# Sheet1.net
KiCad netlist of a schematic drawn in Altium Designer
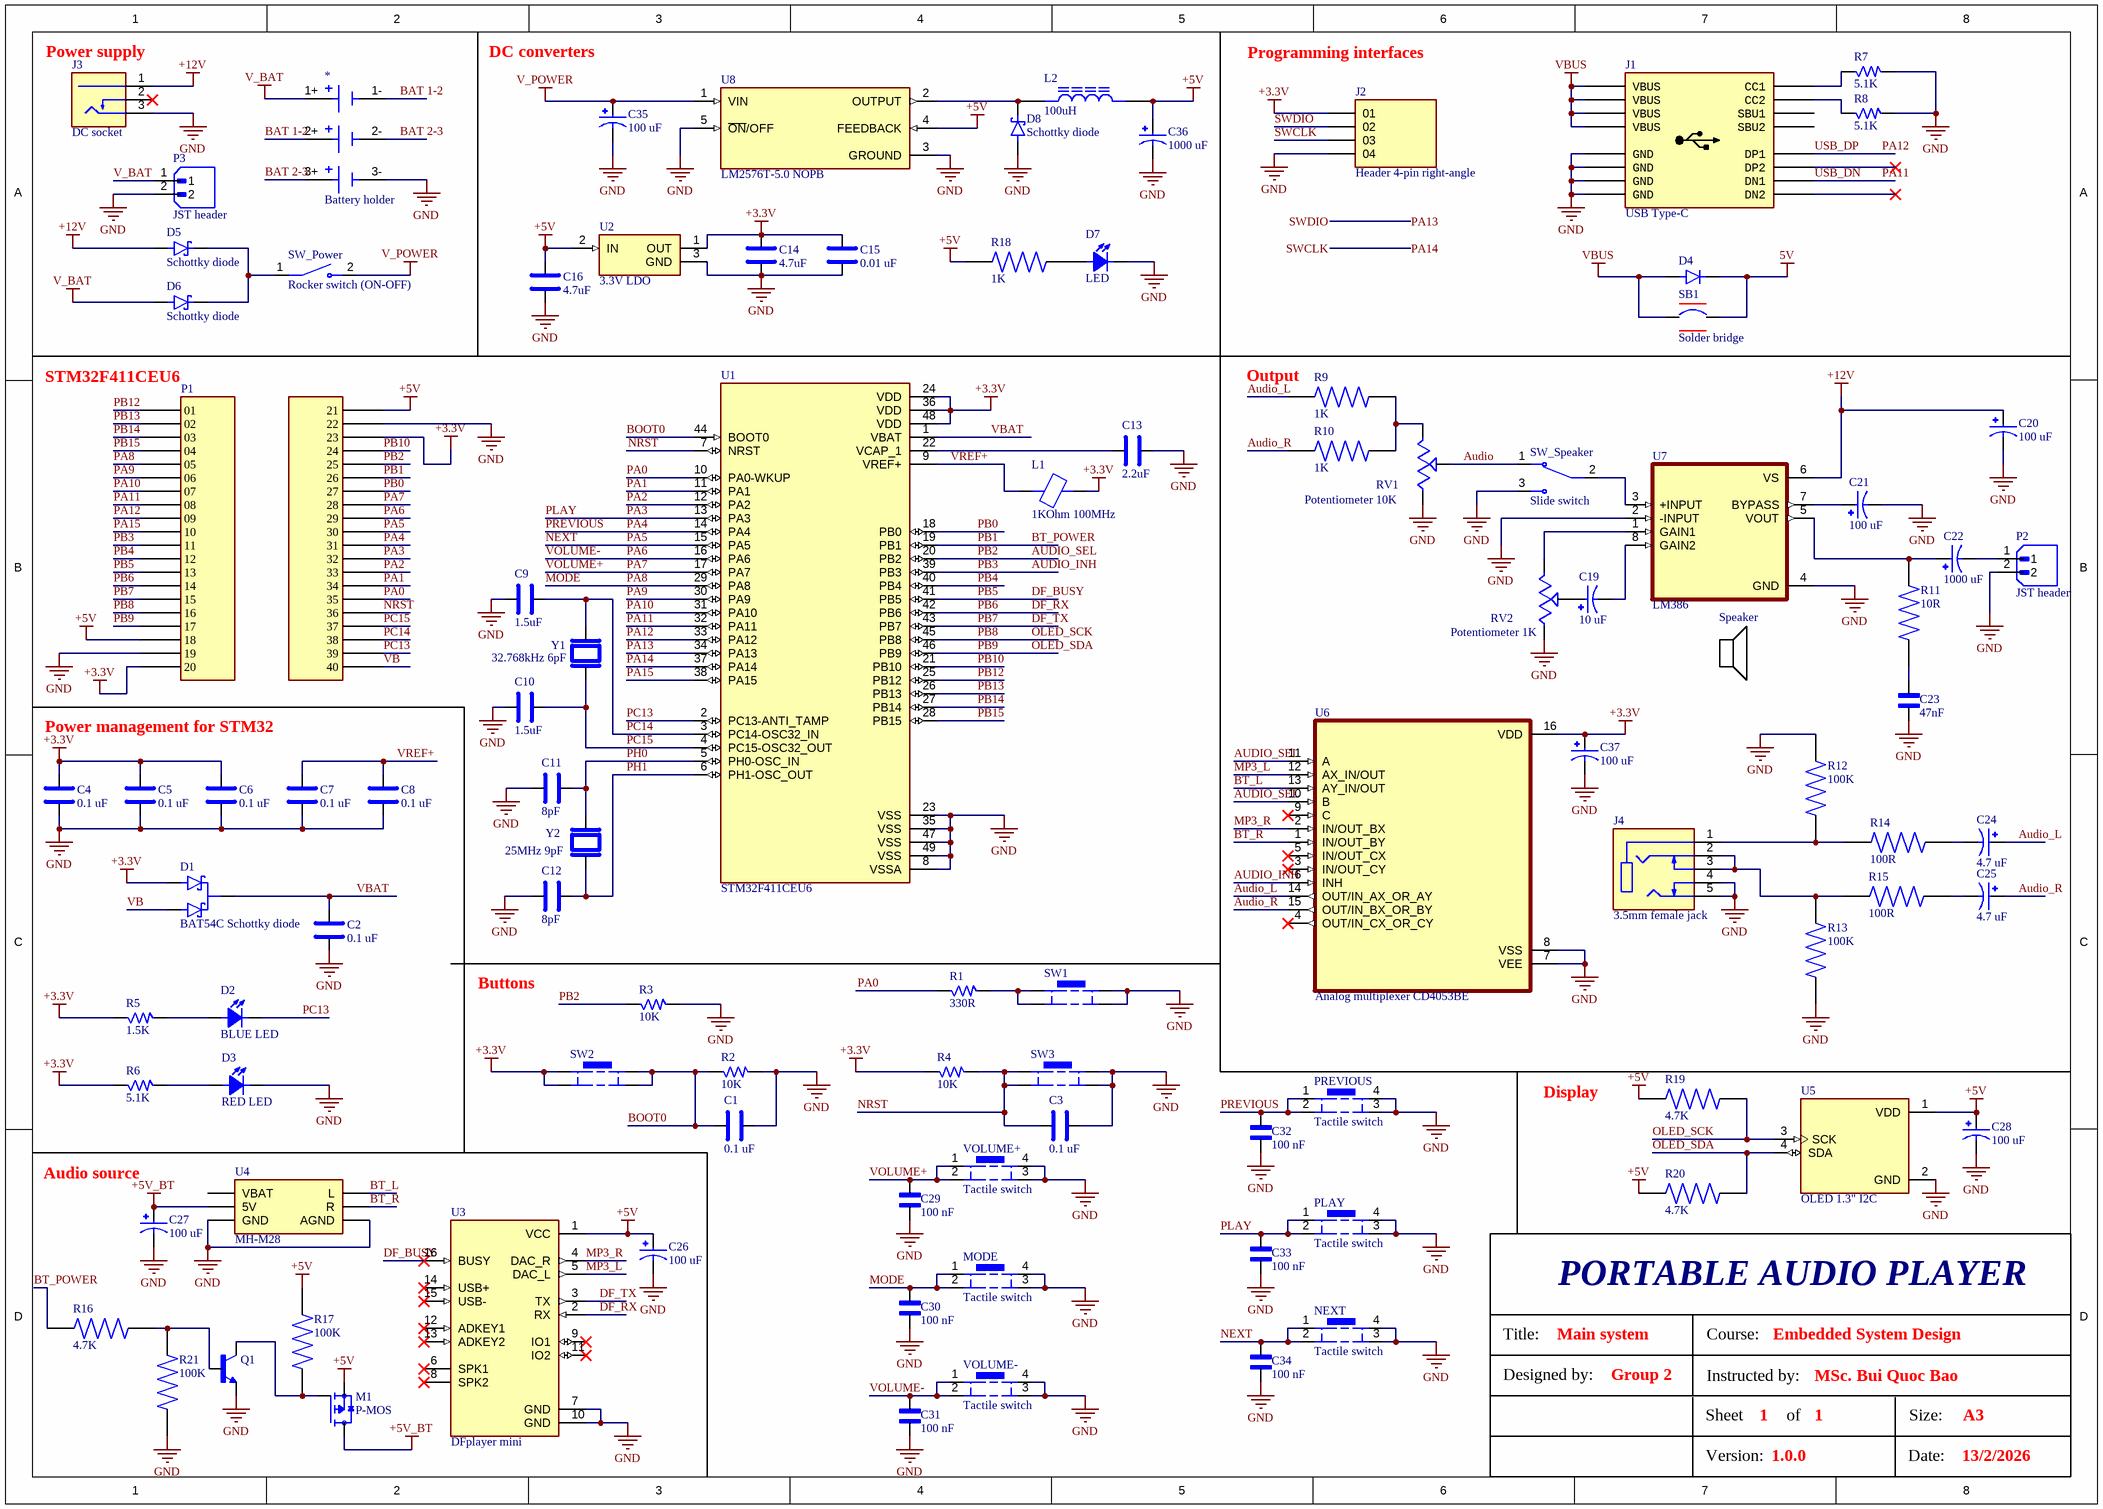
[diagram p0: Sheet1.SchDoc]

(export (version "E")
  (design (tool "Eeschema 10.0.6"))
  (components
    (comp (ref "*")
      (value "Battery holder")
      (footprint "BAT_BK-18650-PC6")
      (libsource (lib "Schlib1") (part "Battery holder"))
    )
    (comp (ref "C1") (value "0.1 uF") (footprint "CAP-CER-0603") (libsource (lib "Schlib1") (part "0.1 uF")))
    (comp (ref "C2") (value "0.1 uF") (footprint "CAP-CER-0603") (libsource (lib "Schlib1") (part "0.1 uF")))
    (comp (ref "C3") (value "0.1 uF") (footprint "CAP-CER-0603") (libsource (lib "Schlib1") (part "0.1 uF")))
    (comp (ref "C4") (value "0.1 uF") (footprint "CAP-CER-0603") (libsource (lib "Schlib1") (part "0.1 uF")))
    (comp (ref "C5") (value "0.1 uF") (footprint "CAP-CER-0603") (libsource (lib "Schlib1") (part "0.1 uF")))
    (comp (ref "C6") (value "0.1 uF") (footprint "CAP-CER-0603") (libsource (lib "Schlib1") (part "0.1 uF")))
    (comp (ref "C7") (value "0.1 uF") (footprint "CAP-CER-0603") (libsource (lib "Schlib1") (part "0.1 uF")))
    (comp (ref "C8") (value "0.1 uF") (footprint "CAP-CER-0603") (libsource (lib "Schlib1") (part "0.1 uF")))
    (comp (ref "C9") (value "1.5uF") (footprint "CAP-CER-0603") (libsource (lib "Schlib1") (part "1.5uF")))
    (comp (ref "C10") (value "1.5uF") (footprint "CAP-CER-0603") (libsource (lib "Schlib1") (part "1.5uF")))
    (comp (ref "C11") (value "8pF") (footprint "CAP-CER-0603") (libsource (lib "Schlib1") (part "8pF")))
    (comp (ref "C12") (value "8pF") (footprint "CAP-CER-0603") (libsource (lib "Schlib1") (part "8pF")))
    (comp (ref "C13") (value "2.2uF") (footprint "CAP-CER-0603") (libsource (lib "Schlib1") (part "2.2uF")))
    (comp (ref "C14") (value "4.7uF") (footprint "CAP-CER-0603") (libsource (lib "Schlib1") (part "4.7uF")))
    (comp (ref "C15")
      (value "0.01 uF")
      (footprint "CAP-CER-0603")
      (libsource (lib "Schlib1") (part "0.01 uF"))
    )
    (comp (ref "C16") (value "4.7uF") (footprint "CAP-CER-0603") (libsource (lib "Schlib1") (part "4.7uF")))
    (comp (ref "C19")
      (value "10 uF")
      (footprint "CAPPRD200W50D500H1100")
      (libsource (lib "Schlib1") (part "10 uF"))
    )
    (comp (ref "C20")
      (value "100 uF")
      (footprint "CAPPRD250W50D630H1120")
      (libsource (lib "") (part "100 uF_1"))
    )
    (comp (ref "C21")
      (value "100 uF")
      (footprint "CAPPRD250W50D630H1120")
      (libsource (lib "Schlib1") (part "100 uF"))
    )
    (comp (ref "C22")
      (value "1000 uF")
      (footprint "CAPPRD500W60D1000H2500")
      (libsource (lib "") (part "1000 uF_1"))
    )
    (comp (ref "C23")
      (value "47nF")
      (footprint "CAPRR254W50L508T317H508")
      (libsource (lib "Schlib1") (part "47nF"))
    )
    (comp (ref "C24")
      (value "4.7 uF")
      (footprint "CAPPRD200W50D500H1100")
      (libsource (lib "Schlib1") (part "4.7 uF"))
    )
    (comp (ref "C25")
      (value "4.7 uF")
      (footprint "CAPPRD200W50D500H1100")
      (libsource (lib "Schlib1") (part "4.7 uF"))
    )
    (comp (ref "C26")
      (value "100 uF")
      (footprint "CAPPRD250W50D630H1120")
      (libsource (lib "") (part "100 uF_1"))
    )
    (comp (ref "C27")
      (value "100 uF")
      (footprint "CAPPRD250W50D630H1120")
      (libsource (lib "") (part "100 uF_1"))
    )
    (comp (ref "C28")
      (value "100 uF")
      (footprint "CAPPRD250W50D630H1120")
      (libsource (lib "") (part "100 uF_1"))
    )
    (comp (ref "C29")
      (value "100 nF")
      (footprint "CAPRR254W54L381T254H466")
      (libsource (lib "Schlib1") (part "100 nF"))
    )
    (comp (ref "C30")
      (value "100 nF")
      (footprint "CAPRR254W54L381T254H466")
      (libsource (lib "Schlib1") (part "100 nF"))
    )
    (comp (ref "C31")
      (value "100 nF")
      (footprint "CAPRR254W54L381T254H466")
      (libsource (lib "Schlib1") (part "100 nF"))
    )
    (comp (ref "C32")
      (value "100 nF")
      (footprint "CAPRR254W54L381T254H466")
      (libsource (lib "Schlib1") (part "100 nF"))
    )
    (comp (ref "C33")
      (value "100 nF")
      (footprint "CAPRR254W54L381T254H466")
      (libsource (lib "Schlib1") (part "100 nF"))
    )
    (comp (ref "C34")
      (value "100 nF")
      (footprint "CAPRR254W54L381T254H466")
      (libsource (lib "Schlib1") (part "100 nF"))
    )
    (comp (ref "C35")
      (value "100 uF")
      (footprint "CAPPRD250W50D630H1120")
      (libsource (lib "") (part "100 uF_1"))
    )
    (comp (ref "C36")
      (value "1000 uF")
      (footprint "CAPPRD500W60D1000H2500")
      (libsource (lib "Schlib1") (part "1000 uF"))
    )
    (comp (ref "C37")
      (value "100 uF")
      (footprint "CAPPRD250W50D630H1120")
      (libsource (lib "") (part "100 uF_1"))
    )
    (comp (ref "D1")
      (value "BAT54C Schottky diode")
      (footprint "SOT95P237X112-3N")
      (libsource (lib "Schlib1") (part "BAT54C Schottky diode"))
    )
    (comp (ref "D2")
      (value "BLUE LED")
      (footprint "LED-SMD-0603")
      (libsource (lib "Schlib1") (part "BLUE LED"))
    )
    (comp (ref "D3")
      (value "RED LED")
      (footprint "LED-SMD-0603")
      (libsource (lib "Schlib1") (part "RED LED"))
    )
    (comp (ref "D4") (value "Diode") (footprint "DIOM5227X270N") (libsource (lib "Schlib1") (part "Diode")))
    (comp (ref "D5")
      (value "Schottky diode")
      (footprint "DIOAD1039W78L463D236")
      (libsource (lib "Schlib1") (part "Schottky diode"))
    )
    (comp (ref "D6")
      (value "Schottky diode")
      (footprint "DIOAD1039W78L463D236")
      (libsource (lib "Schlib1") (part "Schottky diode"))
    )
    (comp (ref "D7") (value "LED") (footprint "LED-TH-2.54mm") (libsource (lib "Schlib1") (part "LED")))
    (comp (ref "D8")
      (value "Schottky diode")
      (footprint "DIOAD1039W78L463D236")
      (libsource (lib "Schlib1") (part "Schottky diode"))
    )
    (comp (ref "J1")
      (value "USB Type-C")
      (footprint "TYPE-C-16POS")
      (libsource (lib "Schlib1") (part "USB Type-C"))
    )
    (comp (ref "J2")
      (value "Header 4-pin right-angle")
      (footprint "SAMTEC_HTSW-104-08-G-S-RA")
      (libsource (lib "Schlib1") (part "Header 4-pin right-angle"))
    )
    (comp (ref "J3")
      (value "DC socket")
      (footprint "GRAVITECH_CON-SOCJ-2155")
      (libsource (lib "Schlib1") (part "DC socket"))
    )
    (comp (ref "J4")
      (value "3.5mm female jack")
      (footprint "CLIFF_FC68133")
      (libsource (lib "Schlib1") (part "3.5mm female jack"))
    )
    (comp (ref "L1")
      (value "1KOhm 100MHz")
      (footprint "FERRITE-0603")
      (libsource (lib "Schlib1") (part "1KOhm 100MHz"))
    )
    (comp (ref "L2")
      (value "100uH")
      (footprint "IND_RLB9012-101KL")
      (libsource (lib "Schlib1") (part "100uH"))
    )
    (comp (ref "M1")
      (value "P-MOS")
      (footprint "TO254P1067X483X2286-3")
      (libsource (lib "Schlib1") (part "P-MOS"))
    )
    (comp (ref "MODE")
      (value "Tactile switch")
      (footprint "Tactice-Switch-TH-12x12")
      (libsource (lib "Schlib1") (part "Tactile switch"))
    )
    (comp (ref "NEXT")
      (value "Tactile switch")
      (footprint "Tactice-Switch-TH-12x12")
      (libsource (lib "Schlib1") (part "Tactile switch"))
    )
    (comp (ref "P1")
      (value "2x20 female header for mounting Blackpill board")
      (footprint "Blackpill board mounting headers")
      (libsource (lib "Schlib1") (part "2x20 female header for mounting Blackpill board"))
    )
    (comp (ref "P2")
      (value "JST header")
      (footprint "JST_B2B-XH-A")
      (libsource (lib "Schlib1") (part "JST header"))
    )
    (comp (ref "P3")
      (value "JST header")
      (footprint "JST_B2B-XH-A")
      (libsource (lib "Schlib1") (part "JST header"))
    )
    (comp (ref "PLAY")
      (value "Tactile switch")
      (footprint "Tactice-Switch-TH-12x12")
      (libsource (lib "Schlib1") (part "Tactile switch"))
    )
    (comp (ref "PREVIOUS")
      (value "Tactile switch")
      (footprint "Tactice-Switch-TH-12x12")
      (libsource (lib "Schlib1") (part "Tactile switch"))
    )
    (comp (ref "Q1")
      (value "NPN transistor")
      (footprint "TO92127P495H495-3")
      (libsource (lib "Schlib1") (part "NPN transistor"))
    )
    (comp (ref "R1") (value "330R") (footprint "RES-SMD-0603") (libsource (lib "Schlib1") (part "330R")))
    (comp (ref "R2") (value "10K") (footprint "RES-SMD-0603") (libsource (lib "Schlib1") (part "10K")))
    (comp (ref "R3") (value "10K") (footprint "RES-SMD-0603") (libsource (lib "Schlib1") (part "10K")))
    (comp (ref "R4") (value "10K") (footprint "RES-SMD-0603") (libsource (lib "Schlib1") (part "10K")))
    (comp (ref "R5") (value "1.5K") (footprint "RES-SMD-0603") (libsource (lib "Schlib1") (part "1.5K")))
    (comp (ref "R6") (value "5.1K") (footprint "RES-SMD-0603") (libsource (lib "Schlib1") (part "5.1K")))
    (comp (ref "R7") (value "5.1K") (footprint "RES-SMD-0603") (libsource (lib "Schlib1") (part "5.1K")))
    (comp (ref "R8") (value "5.1K") (footprint "RES-SMD-0603") (libsource (lib "Schlib1") (part "5.1K")))
    (comp (ref "R9") (value "1K") (footprint "RESAD1100W55L680D260") (libsource (lib "Schlib1") (part "1K")))
    (comp (ref "R10") (value "1K") (footprint "RESAD1100W55L680D260") (libsource (lib "Schlib1") (part "1K")))
    (comp (ref "R11")
      (value "10R")
      (footprint "RESAD1100W55L680D260")
      (libsource (lib "Schlib1") (part "10R"))
    )
    (comp (ref "R12")
      (value "100K")
      (footprint "RESAD1100W55L680D260")
      (libsource (lib "Schlib1") (part "100K"))
    )
    (comp (ref "R13")
      (value "100K")
      (footprint "RESAD1100W55L680D260")
      (libsource (lib "Schlib1") (part "100K"))
    )
    (comp (ref "R14")
      (value "100R")
      (footprint "RESAD1100W55L680D260")
      (libsource (lib "Schlib1") (part "100R"))
    )
    (comp (ref "R15")
      (value "100R")
      (footprint "RESAD1100W55L680D260")
      (libsource (lib "Schlib1") (part "100R"))
    )
    (comp (ref "R16")
      (value "4.7K")
      (footprint "RESAD1100W55L680D260")
      (libsource (lib "Schlib1") (part "4.7K"))
    )
    (comp (ref "R17")
      (value "100K")
      (footprint "RESAD1100W55L680D260")
      (libsource (lib "Schlib1") (part "100K"))
    )
    (comp (ref "R18") (value "1K") (footprint "RESAD1100W55L680D260") (libsource (lib "Schlib1") (part "1K")))
    (comp (ref "R19")
      (value "4.7K")
      (footprint "RESAD1100W55L680D260")
      (libsource (lib "Schlib1") (part "4.7K"))
    )
    (comp (ref "R20")
      (value "4.7K")
      (footprint "RESAD1100W55L680D260")
      (libsource (lib "Schlib1") (part "4.7K"))
    )
    (comp (ref "R21")
      (value "100K")
      (footprint "RESAD1100W55L680D260")
      (libsource (lib "Schlib1") (part "100K"))
    )
    (comp (ref "RV1")
      (value "Potentiometer 10K")
      (footprint "TRIM_WH148-1A-2-18T-L20")
      (libsource (lib "Schlib1") (part "Potentiometer 10K"))
    )
    (comp (ref "RV2")
      (value "Potentiometer 1K")
      (footprint "TRIM_WH148-1A-2-18T-L20")
      (libsource (lib "Schlib1") (part "Potentiometer 1K"))
    )
    (comp (ref "SB1")
      (value "Solder bridge")
      (footprint "SOLDER_BRIDGE")
      (libsource (lib "Schlib1") (part "Solder bridge"))
    )
    (comp (ref "Speaker")
      (value "Speaker")
      (footprint "50mm speaker")
      (libsource (lib "Schlib1") (part "Speaker"))
    )
    (comp (ref "SW1")
      (value "SW_small_rectangular")
      (footprint "SW_SKRPACE010")
      (libsource (lib "Schlib1") (part "SW_small_rectangular"))
    )
    (comp (ref "SW2")
      (value "SW_small_rectangular")
      (footprint "SW_SKRPACE010")
      (libsource (lib "Schlib1") (part "SW_small_rectangular"))
    )
    (comp (ref "SW3")
      (value "SW_small_rectangular")
      (footprint "SW_SKRPACE010")
      (libsource (lib "Schlib1") (part "SW_small_rectangular"))
    )
    (comp (ref "SW_Power")
      (value "Rocker switch (ON-OFF)")
      (footprint "Rocker switch (ON-OFF)")
      (libsource (lib "Schlib1") (part "Rocker switch (ON-OFF)"))
    )
    (comp (ref "SW_Speaker")
      (value "Slide switch")
      (footprint "SW_SLW-1276864-4A-D")
      (libsource (lib "Schlib1") (part "Slide switch"))
    )
    (comp (ref "U1")
      (value "STM32F411CEU6")
      (footprint "QFN50P700X700X60-49N")
      (libsource (lib "Schlib1") (part "STM32F411CEU6"))
    )
    (comp (ref "U2") (value "3.3V LDO") (footprint "SOT23-3") (libsource (lib "Schlib1") (part "3.3V LDO")))
    (comp (ref "U3")
      (value "DFplayer mini")
      (footprint "MODULE_DFR0299")
      (libsource (lib "Schlib1") (part "DFplayer mini"))
    )
    (comp (ref "U4") (value "MH-M28") (footprint "MH-M28") (libsource (lib "Schlib1") (part "MH-M28")))
    (comp (ref "U5")
      (value "OLED 1.3\" I2C")
      (footprint "LCD_OLED_128X64_1.3_I2C")
      (libsource (lib "Schlib1") (part "OLED 1.3{dblquote} I2C"))
    )
    (comp (ref "U6")
      (value "Analog multiplexer CD4053BE")
      (footprint "DIP_16")
      (libsource (lib "Schlib1") (part "Analog multiplexer CD4053BE"))
    )
    (comp (ref "U7") (value "LM386") (footprint "DIP_8") (libsource (lib "Schlib1") (part "LM386")))
    (comp (ref "U8")
      (value "LM2576T-5.0 NOPB")
      (footprint "TO170P1067X483X1651-5")
      (libsource (lib "Schlib1") (part "LM2576T-5.0 NOPB"))
    )
    (comp (ref "VOLUME+")
      (value "Tactile switch")
      (footprint "Tactice-Switch-TH-12x12")
      (libsource (lib "Schlib1") (part "Tactile switch"))
    )
    (comp (ref "VOLUME-")
      (value "Tactile switch")
      (footprint "Tactice-Switch-TH-12x12")
      (libsource (lib "Schlib1") (part "Tactile switch"))
    )
    (comp (ref "Y1")
      (value "32.768kHz 6pF")
      (footprint "XTAL_CM8V-T1A-32.768KHZ-6PF-20PPM-TA-QC")
      (libsource (lib "Schlib1") (part "32.768kHz 6pF"))
    )
    (comp (ref "Y2")
      (value "25MHz 9pF")
      (footprint "XTAL_SXT2249BB16-25.000MT")
      (libsource (lib "Schlib1") (part "25MHz 9pF"))
    )
  )
  (nets
    (net (code "1") (name "+3.3V") (class "Default")
      (node (ref "C14") (pin "2") (pintype "passive"))
      (node (ref "C15") (pin "2") (pintype "passive"))
      (node (ref "C37") (pin "P") (pinfunction "P_P") (pintype "passive"))
      (node (ref "C4") (pin "2") (pintype "passive"))
      (node (ref "C5") (pin "2") (pintype "passive"))
      (node (ref "C6") (pin "2") (pintype "passive"))
      (node (ref "D1") (pin "1") (pinfunction "1_1") (pintype "passive"))
      (node (ref "J2") (pin "01") (pinfunction "01_01") (pintype "passive"))
      (node (ref "L1") (pin "2") (pinfunction "2_2") (pintype "passive"))
      (node (ref "P1") (pin "20") (pinfunction "20_20") (pintype "passive"))
      (node (ref "P1") (pin "23") (pinfunction "23_23") (pintype "passive"))
      (node (ref "R4") (pin "1") (pinfunction "1_1") (pintype "passive"))
      (node (ref "R5") (pin "1") (pinfunction "1_1") (pintype "passive"))
      (node (ref "R6") (pin "1") (pinfunction "1_1") (pintype "passive"))
      (node (ref "SW2") (pin "1") (pintype "passive"))
      (node (ref "SW2") (pin "2") (pintype "passive"))
      (node (ref "U1") (pin "24") (pinfunction "VDD_24") (pintype "power_in"))
      (node (ref "U1") (pin "36") (pinfunction "VDD_36") (pintype "power_in"))
      (node (ref "U1") (pin "48") (pinfunction "VDD_48") (pintype "power_in"))
      (node (ref "U2") (pin "1") (pinfunction "OUT_1") (pintype "power_in"))
      (node (ref "U6") (pin "16") (pinfunction "VDD_16") (pintype "power_in"))
    )
    (net (code "2") (name "+5V") (class "Default")
      (node (ref "C16") (pin "2") (pintype "passive"))
      (node (ref "C26") (pin "P") (pinfunction "P_P") (pintype "passive"))
      (node (ref "C28") (pin "P") (pinfunction "P_P") (pintype "passive"))
      (node (ref "C36") (pin "P") (pinfunction "P_P") (pintype "passive"))
      (node (ref "L2") (pin "2") (pinfunction "2_2") (pintype "passive"))
      (node (ref "M1") (pin "3") (pinfunction "S_3") (pintype "passive"))
      (node (ref "P1") (pin "18") (pinfunction "18_18") (pintype "passive"))
      (node (ref "P1") (pin "21") (pinfunction "21_21") (pintype "passive"))
      (node (ref "R17") (pin "2") (pinfunction "2_2") (pintype "passive"))
      (node (ref "R18") (pin "1") (pinfunction "1_1") (pintype "passive"))
      (node (ref "R19") (pin "2") (pinfunction "2_2") (pintype "passive"))
      (node (ref "R20") (pin "1") (pinfunction "1_1") (pintype "passive"))
      (node (ref "U2") (pin "2") (pinfunction "IN_2") (pintype "input"))
      (node (ref "U3") (pin "1") (pinfunction "VCC_1") (pintype "power_in"))
      (node (ref "U5") (pin "1") (pinfunction "VDD_1") (pintype "power_in"))
      (node (ref "U8") (pin "4") (pinfunction "FEEDBACK_4") (pintype "input"))
    )
    (net (code "3") (name "+5V_BT") (class "Default")
      (node (ref "C27") (pin "P") (pinfunction "P_P") (pintype "passive"))
      (node (ref "M1") (pin "2") (pinfunction "D_2") (pintype "passive"))
      (node (ref "U4") (pin "5V") (pinfunction "5V_5V") (pintype "passive"))
    )
    (net (code "4") (name "+12V") (class "Default")
      (node (ref "C20") (pin "P") (pinfunction "P_P") (pintype "passive"))
      (node (ref "D5") (pin "2") (pinfunction "A_2") (pintype "passive"))
      (node (ref "J3") (pin "1") (pinfunction "1_1") (pintype "passive"))
      (node (ref "U7") (pin "6") (pinfunction "VS_6") (pintype "power_in"))
    )
    (net (code "5") (name "/AUDIO_INH") (class "Default")
      (node (ref "P1") (pin "11") (pinfunction "11_11") (pintype "passive"))
      (node (ref "U1") (pin "39") (pinfunction "PB3_39") (pintype "bidirectional"))
      (node (ref "U6") (pin "6") (pinfunction "INH_6") (pintype "input"))
    )
    (net (code "6") (name "/AUDIO_SEL") (class "Default")
      (node (ref "P1") (pin "25") (pinfunction "25_25") (pintype "passive"))
      (node (ref "R3") (pin "1") (pinfunction "1_1") (pintype "passive"))
      (node (ref "U1") (pin "20") (pinfunction "PB2_20") (pintype "bidirectional"))
      (node (ref "U6") (pin "10") (pinfunction "B_10") (pintype "input"))
      (node (ref "U6") (pin "11") (pinfunction "A_11") (pintype "input"))
    )
    (net (code "7") (name "/Audio") (class "Default")
      (node (ref "RV1") (pin "2") (pinfunction "2_2") (pintype "passive"))
      (node (ref "SW_Speaker") (pin "1") (pinfunction "1_1") (pintype "passive"))
    )
    (net (code "8") (name "/Audio_L") (class "Default")
      (node (ref "C24") (pin "P") (pinfunction "P_P") (pintype "passive"))
      (node (ref "R9") (pin "1") (pinfunction "1_1") (pintype "passive"))
      (node (ref "U6") (pin "14") (pinfunction "OUT/IN_AX_OR_AY_14") (pintype "output"))
    )
    (net (code "9") (name "/Audio_R") (class "Default")
      (node (ref "C25") (pin "P") (pinfunction "P_P") (pintype "passive"))
      (node (ref "R10") (pin "1") (pinfunction "1_1") (pintype "passive"))
      (node (ref "U6") (pin "15") (pinfunction "OUT/IN_BX_OR_BY_15") (pintype "output"))
    )
    (net (code "10") (name "/BAT 1-2") (class "Default")
      (node (ref "*") (pin "1-") (pinfunction "1-_1-") (pintype "passive"))
      (node (ref "*") (pin "2+") (pinfunction "2+_2+") (pintype "passive"))
    )
    (net (code "11") (name "/BAT 2-3") (class "Default")
      (node (ref "*") (pin "2-") (pinfunction "2-_2-") (pintype "passive"))
      (node (ref "*") (pin "3+") (pinfunction "3+_3+") (pintype "passive"))
    )
    (net (code "12") (name "/BOOT0") (class "Default")
      (node (ref "C1") (pin "1") (pintype "passive"))
      (node (ref "R2") (pin "1") (pinfunction "1_1") (pintype "passive"))
      (node (ref "SW2") (pin "3") (pintype "passive"))
      (node (ref "SW2") (pin "4") (pintype "passive"))
      (node (ref "U1") (pin "44") (pinfunction "BOOT0_44") (pintype "input"))
    )
    (net (code "13") (name "/BT_L") (class "Default")
      (node (ref "U4") (pin "L") (pinfunction "L_L") (pintype "passive"))
      (node (ref "U6") (pin "13") (pinfunction "AY_IN/OUT_13") (pintype "input"))
    )
    (net (code "14") (name "/BT_POWER") (class "Default")
      (node (ref "P1") (pin "26") (pinfunction "26_26") (pintype "passive"))
      (node (ref "R16") (pin "1") (pinfunction "1_1") (pintype "passive"))
      (node (ref "U1") (pin "19") (pinfunction "PB1_19") (pintype "bidirectional"))
    )
    (net (code "15") (name "/BT_R") (class "Default")
      (node (ref "U4") (pin "R") (pinfunction "R_R") (pintype "passive"))
      (node (ref "U6") (pin "1") (pinfunction "IN/OUT_BY_1") (pintype "input"))
    )
    (net (code "16") (name "/DF_BUSY") (class "Default")
      (node (ref "P1") (pin "13") (pinfunction "13_13") (pintype "passive"))
      (node (ref "U1") (pin "41") (pinfunction "PB5_41") (pintype "bidirectional"))
      (node (ref "U3") (pin "16") (pinfunction "BUSY_16") (pintype "input"))
    )
    (net (code "17") (name "/DF_RX") (class "Default")
      (node (ref "P1") (pin "14") (pinfunction "14_14") (pintype "passive"))
      (node (ref "U1") (pin "42") (pinfunction "PB6_42") (pintype "bidirectional"))
      (node (ref "U3") (pin "2") (pinfunction "RX_2") (pintype "input"))
    )
    (net (code "18") (name "/DF_TX") (class "Default")
      (node (ref "P1") (pin "15") (pinfunction "15_15") (pintype "passive"))
      (node (ref "U1") (pin "43") (pinfunction "PB7_43") (pintype "bidirectional"))
      (node (ref "U3") (pin "3") (pinfunction "TX_3") (pintype "output"))
    )
    (net (code "19") (name "/MODE") (class "Default")
      (node (ref "C30") (pin "2") (pinfunction "2_2") (pintype "passive"))
      (node (ref "MODE") (pin "1") (pinfunction "1_1") (pintype "passive"))
      (node (ref "MODE") (pin "2") (pinfunction "2_2") (pintype "passive"))
      (node (ref "P1") (pin "5") (pinfunction "05_5") (pintype "passive"))
      (node (ref "U1") (pin "29") (pinfunction "PA8_29") (pintype "bidirectional"))
    )
    (net (code "20") (name "/MP3_L") (class "Default")
      (node (ref "U3") (pin "5") (pinfunction "DAC_L_5") (pintype "output"))
      (node (ref "U6") (pin "12") (pinfunction "AX_IN/OUT_12") (pintype "input"))
    )
    (net (code "21") (name "/MP3_R") (class "Default")
      (node (ref "U3") (pin "4") (pinfunction "DAC_R_4") (pintype "output"))
      (node (ref "U6") (pin "2") (pinfunction "IN/OUT_BX_2") (pintype "input"))
    )
    (net (code "22") (name "/NEXT") (class "Default")
      (node (ref "C34") (pin "2") (pinfunction "2_2") (pintype "passive"))
      (node (ref "NEXT") (pin "1") (pinfunction "1_1") (pintype "passive"))
      (node (ref "NEXT") (pin "2") (pinfunction "2_2") (pintype "passive"))
      (node (ref "P1") (pin "30") (pinfunction "30_30") (pintype "passive"))
      (node (ref "U1") (pin "15") (pinfunction "PA5_15") (pintype "bidirectional"))
    )
    (net (code "23") (name "/NRST") (class "Default")
      (node (ref "C3") (pin "1") (pintype "passive"))
      (node (ref "P1") (pin "36") (pinfunction "36_36") (pintype "passive"))
      (node (ref "R4") (pin "2") (pinfunction "2_2") (pintype "passive"))
      (node (ref "SW3") (pin "1") (pintype "passive"))
      (node (ref "SW3") (pin "2") (pintype "passive"))
      (node (ref "U1") (pin "7") (pinfunction "NRST_7") (pintype "bidirectional"))
    )
    (net (code "24") (name "/OLED_SCK") (class "Default")
      (node (ref "P1") (pin "16") (pinfunction "16_16") (pintype "passive"))
      (node (ref "R19") (pin "1") (pinfunction "1_1") (pintype "passive"))
      (node (ref "U1") (pin "45") (pinfunction "PB8_45") (pintype "bidirectional"))
      (node (ref "U5") (pin "3") (pinfunction "SCK_3") (pintype "input"))
    )
    (net (code "25") (name "/OLED_SDA") (class "Default")
      (node (ref "P1") (pin "17") (pinfunction "17_17") (pintype "passive"))
      (node (ref "R20") (pin "2") (pinfunction "2_2") (pintype "passive"))
      (node (ref "U1") (pin "46") (pinfunction "PB9_46") (pintype "bidirectional"))
      (node (ref "U5") (pin "4") (pinfunction "SDA_4") (pintype "bidirectional"))
    )
    (net (code "26") (name "/PA0") (class "Default")
      (node (ref "P1") (pin "35") (pinfunction "35_35") (pintype "passive"))
      (node (ref "R1") (pin "1") (pinfunction "1_1") (pintype "passive"))
      (node (ref "U1") (pin "10") (pinfunction "PA0-WKUP_10") (pintype "bidirectional"))
    )
    (net (code "27") (name "/PA1") (class "Default")
      (node (ref "P1") (pin "34") (pinfunction "34_34") (pintype "passive"))
      (node (ref "U1") (pin "11") (pinfunction "PA1_11") (pintype "bidirectional"))
    )
    (net (code "28") (name "/PA2") (class "Default")
      (node (ref "P1") (pin "33") (pinfunction "33_33") (pintype "passive"))
      (node (ref "U1") (pin "12") (pinfunction "PA2_12") (pintype "bidirectional"))
    )
    (net (code "29") (name "/PA3") (class "Default")
      (node (ref "C33") (pin "2") (pinfunction "2_2") (pintype "passive"))
      (node (ref "P1") (pin "32") (pinfunction "32_32") (pintype "passive"))
      (node (ref "PLAY") (pin "1") (pinfunction "1_1") (pintype "passive"))
      (node (ref "PLAY") (pin "2") (pinfunction "2_2") (pintype "passive"))
      (node (ref "U1") (pin "13") (pinfunction "PA3_13") (pintype "bidirectional"))
    )
    (net (code "30") (name "/PA4") (class "Default")
      (node (ref "C32") (pin "2") (pinfunction "2_2") (pintype "passive"))
      (node (ref "P1") (pin "31") (pinfunction "31_31") (pintype "passive"))
      (node (ref "PREVIOUS") (pin "1") (pinfunction "1_1") (pintype "passive"))
      (node (ref "PREVIOUS") (pin "2") (pinfunction "2_2") (pintype "passive"))
      (node (ref "U1") (pin "14") (pinfunction "PA4_14") (pintype "bidirectional"))
    )
    (net (code "31") (name "/PA6") (class "Default")
      (node (ref "C31") (pin "2") (pinfunction "2_2") (pintype "passive"))
      (node (ref "P1") (pin "29") (pinfunction "29_29") (pintype "passive"))
      (node (ref "U1") (pin "16") (pinfunction "PA6_16") (pintype "bidirectional"))
      (node (ref "VOLUME-") (pin "1") (pinfunction "1_1") (pintype "passive"))
      (node (ref "VOLUME-") (pin "2") (pinfunction "2_2") (pintype "passive"))
    )
    (net (code "32") (name "/PA7") (class "Default")
      (node (ref "C29") (pin "2") (pinfunction "2_2") (pintype "passive"))
      (node (ref "P1") (pin "28") (pinfunction "28_28") (pintype "passive"))
      (node (ref "U1") (pin "17") (pinfunction "PA7_17") (pintype "bidirectional"))
      (node (ref "VOLUME+") (pin "1") (pinfunction "1_1") (pintype "passive"))
      (node (ref "VOLUME+") (pin "2") (pinfunction "2_2") (pintype "passive"))
    )
    (net (code "33") (name "/PA9") (class "Default")
      (node (ref "P1") (pin "6") (pinfunction "06_6") (pintype "passive"))
      (node (ref "U1") (pin "30") (pinfunction "PA9_30") (pintype "bidirectional"))
    )
    (net (code "34") (name "/PA10") (class "Default")
      (node (ref "P1") (pin "7") (pinfunction "07_7") (pintype "passive"))
      (node (ref "U1") (pin "31") (pinfunction "PA10_31") (pintype "bidirectional"))
    )
    (net (code "35") (name "/PA11") (class "Default")
      (node (ref "J1") (pin "A7") (pinfunction "DN1_A7") (pintype "passive"))
      (node (ref "P1") (pin "8") (pinfunction "08_8") (pintype "passive"))
      (node (ref "U1") (pin "32") (pinfunction "PA11_32") (pintype "bidirectional"))
    )
    (net (code "36") (name "/PA12") (class "Default")
      (node (ref "J1") (pin "A6") (pinfunction "DP1_A6") (pintype "passive"))
      (node (ref "P1") (pin "9") (pinfunction "09_9") (pintype "passive"))
      (node (ref "U1") (pin "33") (pinfunction "PA12_33") (pintype "bidirectional"))
    )
    (net (code "37") (name "/PA13") (class "Default")
      (node (ref "J2") (pin "02") (pinfunction "02_02") (pintype "passive"))
      (node (ref "U1") (pin "34") (pinfunction "PA13_34") (pintype "bidirectional"))
    )
    (net (code "38") (name "/PA14") (class "Default")
      (node (ref "J2") (pin "03") (pinfunction "03_03") (pintype "passive"))
      (node (ref "U1") (pin "37") (pinfunction "PA14_37") (pintype "bidirectional"))
    )
    (net (code "39") (name "/PA15") (class "Default")
      (node (ref "P1") (pin "10") (pinfunction "10_10") (pintype "passive"))
      (node (ref "U1") (pin "38") (pinfunction "PA15_38") (pintype "bidirectional"))
    )
    (net (code "40") (name "/PB0") (class "Default")
      (node (ref "P1") (pin "27") (pinfunction "27_27") (pintype "passive"))
      (node (ref "U1") (pin "18") (pinfunction "PB0_18") (pintype "bidirectional"))
    )
    (net (code "41") (name "/PB4") (class "Default")
      (node (ref "P1") (pin "12") (pinfunction "12_12") (pintype "passive"))
      (node (ref "U1") (pin "40") (pinfunction "PB4_40") (pintype "bidirectional"))
    )
    (net (code "42") (name "/PB10") (class "Default")
      (node (ref "P1") (pin "24") (pinfunction "24_24") (pintype "passive"))
      (node (ref "U1") (pin "21") (pinfunction "PB10_21") (pintype "bidirectional"))
    )
    (net (code "43") (name "/PB12") (class "Default")
      (node (ref "P1") (pin "1") (pinfunction "01_1") (pintype "passive"))
      (node (ref "U1") (pin "25") (pinfunction "PB12_25") (pintype "bidirectional"))
    )
    (net (code "44") (name "/PB13") (class "Default")
      (node (ref "P1") (pin "2") (pinfunction "02_2") (pintype "passive"))
      (node (ref "U1") (pin "26") (pinfunction "PB13_26") (pintype "bidirectional"))
    )
    (net (code "45") (name "/PB14") (class "Default")
      (node (ref "P1") (pin "3") (pinfunction "03_3") (pintype "passive"))
      (node (ref "U1") (pin "27") (pinfunction "PB14_27") (pintype "bidirectional"))
    )
    (net (code "46") (name "/PB15") (class "Default")
      (node (ref "P1") (pin "4") (pinfunction "04_4") (pintype "passive"))
      (node (ref "U1") (pin "28") (pinfunction "PB15_28") (pintype "bidirectional"))
    )
    (net (code "47") (name "/PC13") (class "Default")
      (node (ref "D2") (pin "2") (pinfunction "K_2") (pintype "passive"))
      (node (ref "P1") (pin "39") (pinfunction "39_39") (pintype "passive"))
      (node (ref "U1") (pin "2") (pinfunction "PC13-ANTI_TAMP_2") (pintype "bidirectional"))
    )
    (net (code "48") (name "/PC14") (class "Default")
      (node (ref "C9") (pin "2") (pintype "passive"))
      (node (ref "P1") (pin "38") (pinfunction "38_38") (pintype "passive"))
      (node (ref "U1") (pin "3") (pinfunction "PC14-OSC32_IN_3") (pintype "bidirectional"))
      (node (ref "Y1") (pin "2") (pinfunction "2_2") (pintype "passive"))
    )
    (net (code "49") (name "/PC15") (class "Default")
      (node (ref "C10") (pin "2") (pintype "passive"))
      (node (ref "P1") (pin "37") (pinfunction "37_37") (pintype "passive"))
      (node (ref "U1") (pin "4") (pinfunction "PC15-OSC32_OUT_4") (pintype "bidirectional"))
      (node (ref "Y1") (pin "1") (pinfunction "1_1") (pintype "passive"))
    )
    (net (code "50") (name "/PH0") (class "Default")
      (node (ref "C11") (pin "2") (pintype "passive"))
      (node (ref "U1") (pin "5") (pinfunction "PH0-OSC_IN_5") (pintype "bidirectional"))
      (node (ref "Y2") (pin "3") (pinfunction "3_3") (pintype "passive"))
    )
    (net (code "51") (name "/PH1") (class "Default")
      (node (ref "C12") (pin "2") (pintype "passive"))
      (node (ref "U1") (pin "6") (pinfunction "PH1-OSC_OUT_6") (pintype "bidirectional"))
      (node (ref "Y2") (pin "1") (pinfunction "1_1") (pintype "passive"))
    )
    (net (code "52") (name "/VB") (class "Default")
      (node (ref "D1") (pin "2") (pinfunction "2_2") (pintype "passive"))
      (node (ref "P1") (pin "40") (pinfunction "40_40") (pintype "passive"))
    )
    (net (code "53") (name "/VBAT") (class "Default")
      (node (ref "C2") (pin "2") (pintype "passive"))
      (node (ref "D1") (pin "3") (pinfunction "3_3") (pintype "passive"))
      (node (ref "U1") (pin "1") (pinfunction "VBAT_1") (pintype "power_in"))
    )
    (net (code "54") (name "/VREF+") (class "Default")
      (node (ref "C7") (pin "2") (pintype "passive"))
      (node (ref "C8") (pin "2") (pintype "passive"))
      (node (ref "L1") (pin "1") (pinfunction "1_1") (pintype "passive"))
      (node (ref "U1") (pin "9") (pinfunction "VREF+_9") (pintype "power_in"))
    )
    (net (code "55") (name "5V") (class "Default")
      (node (ref "D4") (pin "C") (pinfunction "K_C") (pintype "passive"))
      (node (ref "SB1") (pin "2") (pinfunction "2_2") (pintype "passive"))
    )
    (net (code "56") (name "GND") (class "Default")
      (node (ref "*") (pin "3-") (pinfunction "3-_3-") (pintype "passive"))
      (node (ref "C1") (pin "2") (pintype "passive"))
      (node (ref "C10") (pin "1") (pintype "passive"))
      (node (ref "C11") (pin "1") (pintype "passive"))
      (node (ref "C12") (pin "1") (pintype "passive"))
      (node (ref "C13") (pin "2") (pintype "passive"))
      (node (ref "C14") (pin "1") (pintype "passive"))
      (node (ref "C15") (pin "1") (pintype "passive"))
      (node (ref "C16") (pin "1") (pintype "passive"))
      (node (ref "C2") (pin "1") (pintype "passive"))
      (node (ref "C20") (pin "N") (pinfunction "N_N") (pintype "passive"))
      (node (ref "C21") (pin "N") (pinfunction "N_N") (pintype "passive"))
      (node (ref "C23") (pin "1") (pinfunction "1_1") (pintype "passive"))
      (node (ref "C26") (pin "N") (pinfunction "N_N") (pintype "passive"))
      (node (ref "C27") (pin "N") (pinfunction "N_N") (pintype "passive"))
      (node (ref "C28") (pin "N") (pinfunction "N_N") (pintype "passive"))
      (node (ref "C29") (pin "1") (pinfunction "1_1") (pintype "passive"))
      (node (ref "C3") (pin "2") (pintype "passive"))
      (node (ref "C30") (pin "1") (pinfunction "1_1") (pintype "passive"))
      (node (ref "C31") (pin "1") (pinfunction "1_1") (pintype "passive"))
      (node (ref "C32") (pin "1") (pinfunction "1_1") (pintype "passive"))
      (node (ref "C33") (pin "1") (pinfunction "1_1") (pintype "passive"))
      (node (ref "C34") (pin "1") (pinfunction "1_1") (pintype "passive"))
      (node (ref "C35") (pin "N") (pinfunction "N_N") (pintype "passive"))
      (node (ref "C36") (pin "N") (pinfunction "N_N") (pintype "passive"))
      (node (ref "C37") (pin "N") (pinfunction "N_N") (pintype "passive"))
      (node (ref "C4") (pin "1") (pintype "passive"))
      (node (ref "C5") (pin "1") (pintype "passive"))
      (node (ref "C6") (pin "1") (pintype "passive"))
      (node (ref "C7") (pin "1") (pintype "passive"))
      (node (ref "C8") (pin "1") (pintype "passive"))
      (node (ref "C9") (pin "1") (pintype "passive"))
      (node (ref "D3") (pin "2") (pinfunction "K_2") (pintype "passive"))
      (node (ref "D7") (pin "2") (pinfunction "K_2") (pintype "passive"))
      (node (ref "D8") (pin "2") (pinfunction "A_2") (pintype "passive"))
      (node (ref "J1") (pin "A12_B1") (pinfunction "GND_A12_B1") (pintype "passive"))
      (node (ref "J1") (pin "A1_B12") (pinfunction "GND_A1_B12") (pintype "passive"))
      (node (ref "J2") (pin "04") (pinfunction "04_04") (pintype "passive"))
      (node (ref "J3") (pin "3") (pinfunction "3_3") (pintype "passive"))
      (node (ref "J4") (pin "4") (pinfunction "4_4") (pintype "passive"))
      (node (ref "J4") (pin "5") (pinfunction "5_5") (pintype "passive"))
      (node (ref "MODE") (pin "3") (pinfunction "3_3") (pintype "passive"))
      (node (ref "MODE") (pin "4") (pinfunction "4_4") (pintype "passive"))
      (node (ref "NEXT") (pin "3") (pinfunction "3_3") (pintype "passive"))
      (node (ref "NEXT") (pin "4") (pinfunction "4_4") (pintype "passive"))
      (node (ref "P1") (pin "19") (pinfunction "19_19") (pintype "passive"))
      (node (ref "P1") (pin "22") (pinfunction "22_22") (pintype "passive"))
      (node (ref "P2") (pin "2") (pinfunction "2_2") (pintype "passive"))
      (node (ref "P3") (pin "2") (pinfunction "2_2") (pintype "passive"))
      (node (ref "PLAY") (pin "3") (pinfunction "3_3") (pintype "passive"))
      (node (ref "PLAY") (pin "4") (pinfunction "4_4") (pintype "passive"))
      (node (ref "PREVIOUS") (pin "3") (pinfunction "3_3") (pintype "passive"))
      (node (ref "PREVIOUS") (pin "4") (pinfunction "4_4") (pintype "passive"))
      (node (ref "Q1") (pin "1") (pinfunction "E_1") (pintype "passive"))
      (node (ref "R12") (pin "2") (pinfunction "2_2") (pintype "passive"))
      (node (ref "R13") (pin "2") (pinfunction "2_2") (pintype "passive"))
      (node (ref "R2") (pin "2") (pinfunction "2_2") (pintype "passive"))
      (node (ref "R21") (pin "1") (pinfunction "1_1") (pintype "passive"))
      (node (ref "R3") (pin "2") (pinfunction "2_2") (pintype "passive"))
      (node (ref "R7") (pin "2") (pinfunction "2_2") (pintype "passive"))
      (node (ref "R8") (pin "2") (pinfunction "2_2") (pintype "passive"))
      (node (ref "RV1") (pin "3") (pinfunction "3_3") (pintype "passive"))
      (node (ref "RV2") (pin "3") (pinfunction "3_3") (pintype "passive"))
      (node (ref "SW1") (pin "3") (pintype "passive"))
      (node (ref "SW1") (pin "4") (pintype "passive"))
      (node (ref "SW3") (pin "3") (pintype "passive"))
      (node (ref "SW3") (pin "4") (pintype "passive"))
      (node (ref "SW_Speaker") (pin "3") (pinfunction "3_3") (pintype "passive"))
      (node (ref "U1") (pin "23") (pinfunction "VSS_23") (pintype "power_in"))
      (node (ref "U1") (pin "35") (pinfunction "VSS_35") (pintype "power_in"))
      (node (ref "U1") (pin "47") (pinfunction "VSS_47") (pintype "power_in"))
      (node (ref "U1") (pin "49") (pinfunction "VSS_49") (pintype "power_in"))
      (node (ref "U1") (pin "8") (pinfunction "VSSA_8") (pintype "power_in"))
      (node (ref "U2") (pin "3") (pinfunction "GND_3") (pintype "power_in"))
      (node (ref "U3") (pin "10") (pinfunction "GND_10") (pintype "power_in"))
      (node (ref "U3") (pin "7") (pinfunction "GND_7") (pintype "power_in"))
      (node (ref "U4") (pin "AGND") (pinfunction "AGND_AGND") (pintype "passive"))
      (node (ref "U4") (pin "GND") (pinfunction "GND_GND") (pintype "passive"))
      (node (ref "U5") (pin "2") (pinfunction "GND_2") (pintype "power_in"))
      (node (ref "U6") (pin "7") (pinfunction "VEE_7") (pintype "power_in"))
      (node (ref "U6") (pin "8") (pinfunction "VSS_8") (pintype "power_in"))
      (node (ref "U7") (pin "2") (pinfunction "-INPUT_2") (pintype "input"))
      (node (ref "U7") (pin "4") (pinfunction "GND_4") (pintype "power_in"))
      (node (ref "U8") (pin "3") (pinfunction "GROUND_3") (pintype "power_in"))
      (node (ref "U8") (pin "5") (pinfunction "~{ON}/OFF_5") (pintype "input"))
      (node (ref "VOLUME+") (pin "3") (pinfunction "3_3") (pintype "passive"))
      (node (ref "VOLUME+") (pin "4") (pinfunction "4_4") (pintype "passive"))
      (node (ref "VOLUME-") (pin "3") (pinfunction "3_3") (pintype "passive"))
      (node (ref "VOLUME-") (pin "4") (pinfunction "4_4") (pintype "passive"))
    )
    (net (code "57") (name "Net-(C19-PadP)") (class "Default")
      (node (ref "C19") (pin "P") (pinfunction "P_P") (pintype "passive"))
      (node (ref "RV2") (pin "2") (pinfunction "2_2") (pintype "passive"))
    )
    (net (code "58") (name "Net-(C22-PadN)") (class "Default")
      (node (ref "C22") (pin "N") (pinfunction "N_N") (pintype "passive"))
      (node (ref "P2") (pin "1") (pinfunction "1_1") (pintype "passive"))
    )
    (net (code "59") (name "Net-(C23-Pad2)") (class "Default")
      (node (ref "C23") (pin "2") (pinfunction "2_2") (pintype "passive"))
      (node (ref "R11") (pin "2") (pinfunction "2_2") (pintype "passive"))
    )
    (net (code "60") (name "Net-(C24-PadN)") (class "Default")
      (node (ref "C24") (pin "N") (pinfunction "N_N") (pintype "passive"))
      (node (ref "R14") (pin "2") (pinfunction "2_2") (pintype "passive"))
    )
    (net (code "61") (name "Net-(C25-PadN)") (class "Default")
      (node (ref "C25") (pin "N") (pinfunction "N_N") (pintype "passive"))
      (node (ref "R15") (pin "2") (pinfunction "2_2") (pintype "passive"))
    )
    (net (code "62") (name "Net-(D2-A)") (class "Default")
      (node (ref "D2") (pin "1") (pinfunction "A_1") (pintype "passive"))
      (node (ref "R5") (pin "2") (pinfunction "2_2") (pintype "passive"))
    )
    (net (code "63") (name "Net-(D3-A)") (class "Default")
      (node (ref "D3") (pin "1") (pinfunction "A_1") (pintype "passive"))
      (node (ref "R6") (pin "2") (pinfunction "2_2") (pintype "passive"))
    )
    (net (code "64") (name "Net-(D5-K)") (class "Default")
      (node (ref "D5") (pin "1") (pinfunction "K_1") (pintype "passive"))
      (node (ref "D6") (pin "1") (pinfunction "K_1") (pintype "passive"))
      (node (ref "SW_Power") (pin "1") (pinfunction "1_1") (pintype "passive"))
    )
    (net (code "65") (name "Net-(D7-A)") (class "Default")
      (node (ref "D7") (pin "1") (pinfunction "A_1") (pintype "passive"))
      (node (ref "R18") (pin "2") (pinfunction "2_2") (pintype "passive"))
    )
    (net (code "66") (name "Net-(D8-K)") (class "Default")
      (node (ref "D8") (pin "1") (pinfunction "K_1") (pintype "passive"))
      (node (ref "L2") (pin "1") (pinfunction "1_1") (pintype "passive"))
      (node (ref "U8") (pin "2") (pinfunction "OUTPUT_2") (pintype "output"))
    )
    (net (code "67") (name "Net-(J1-CC1)") (class "Default")
      (node (ref "J1") (pin "A5") (pinfunction "CC1_A5") (pintype "passive"))
      (node (ref "R7") (pin "1") (pinfunction "1_1") (pintype "passive"))
    )
    (net (code "68") (name "Net-(J1-CC2)") (class "Default")
      (node (ref "J1") (pin "B5") (pinfunction "CC2_B5") (pintype "passive"))
      (node (ref "R8") (pin "1") (pinfunction "1_1") (pintype "passive"))
    )
    (net (code "69") (name "Net-(J4-Pad1)") (class "Default")
      (node (ref "J4") (pin "1") (pinfunction "1_1") (pintype "passive"))
      (node (ref "R12") (pin "1") (pinfunction "1_1") (pintype "passive"))
      (node (ref "R14") (pin "1") (pinfunction "1_1") (pintype "passive"))
    )
    (net (code "70") (name "Net-(J4-Pad2)") (class "Default")
      (node (ref "J4") (pin "2") (pinfunction "2_2") (pintype "passive"))
      (node (ref "J4") (pin "3") (pinfunction "3_3") (pintype "passive"))
      (node (ref "R13") (pin "1") (pinfunction "1_1") (pintype "passive"))
      (node (ref "R15") (pin "1") (pinfunction "1_1") (pintype "passive"))
    )
    (net (code "71") (name "Net-(M1-G)") (class "Default")
      (node (ref "M1") (pin "1") (pinfunction "G_1") (pintype "passive"))
      (node (ref "Q1") (pin "3") (pinfunction "C_3") (pintype "passive"))
      (node (ref "R17") (pin "1") (pinfunction "1_1") (pintype "passive"))
    )
    (net (code "72") (name "Net-(Q1-B)") (class "Default")
      (node (ref "Q1") (pin "2") (pinfunction "B_2") (pintype "passive"))
      (node (ref "R16") (pin "2") (pinfunction "2_2") (pintype "passive"))
      (node (ref "R21") (pin "2") (pinfunction "2_2") (pintype "passive"))
    )
    (net (code "73") (name "Net-(R1-Pad2)") (class "Default")
      (node (ref "R1") (pin "2") (pinfunction "2_2") (pintype "passive"))
      (node (ref "SW1") (pin "1") (pintype "passive"))
      (node (ref "SW1") (pin "2") (pintype "passive"))
    )
    (net (code "74") (name "Net-(R10-Pad2)") (class "Default")
      (node (ref "R10") (pin "2") (pinfunction "2_2") (pintype "passive"))
      (node (ref "R9") (pin "2") (pinfunction "2_2") (pintype "passive"))
      (node (ref "RV1") (pin "1") (pinfunction "1_1") (pintype "passive"))
    )
    (net (code "75") (name "Net-(U1-VCAP_1)") (class "Default")
      (node (ref "C13") (pin "1") (pintype "passive"))
      (node (ref "U1") (pin "22") (pinfunction "VCAP_1_22") (pintype "power_in"))
    )
    (net (code "76") (name "Net-(U7-+INPUT)") (class "Default")
      (node (ref "SW_Speaker") (pin "2") (pinfunction "2_2") (pintype "passive"))
      (node (ref "U7") (pin "3") (pinfunction "+INPUT_3") (pintype "input"))
    )
    (net (code "77") (name "Net-(U7-BYPASS)") (class "Default")
      (node (ref "C21") (pin "P") (pinfunction "P_P") (pintype "passive"))
      (node (ref "U7") (pin "7") (pinfunction "BYPASS_7") (pintype "output"))
    )
    (net (code "78") (name "Net-(U7-GAIN1)") (class "Default")
      (node (ref "RV2") (pin "1") (pinfunction "1_1") (pintype "passive"))
      (node (ref "U7") (pin "1") (pinfunction "GAIN1_1") (pintype "input"))
    )
    (net (code "79") (name "Net-(U7-GAIN2)") (class "Default")
      (node (ref "C19") (pin "N") (pinfunction "N_N") (pintype "passive"))
      (node (ref "U7") (pin "8") (pinfunction "GAIN2_8") (pintype "input"))
    )
    (net (code "80") (name "Net-(U7-VOUT)") (class "Default")
      (node (ref "C22") (pin "P") (pinfunction "P_P") (pintype "passive"))
      (node (ref "R11") (pin "1") (pinfunction "1_1") (pintype "passive"))
      (node (ref "U7") (pin "5") (pinfunction "VOUT_5") (pintype "output"))
    )
    (net (code "81") (name "VBUS") (class "Default")
      (node (ref "D4") (pin "A") (pinfunction "A_A") (pintype "passive"))
      (node (ref "J1") (pin "A4_B9") (pinfunction "VBUS_A4_B9") (pintype "passive"))
      (node (ref "J1") (pin "A9_B4") (pinfunction "VBUS_A9_B4") (pintype "passive"))
      (node (ref "SB1") (pin "1") (pinfunction "1_1") (pintype "passive"))
    )
    (net (code "82") (name "V_BAT") (class "Default")
      (node (ref "*") (pin "1+") (pinfunction "1+_1+") (pintype "passive"))
      (node (ref "D6") (pin "2") (pinfunction "A_2") (pintype "passive"))
      (node (ref "P3") (pin "1") (pinfunction "1_1") (pintype "passive"))
    )
    (net (code "83") (name "V_POWER") (class "Default")
      (node (ref "C35") (pin "P") (pinfunction "P_P") (pintype "passive"))
      (node (ref "SW_Power") (pin "2") (pinfunction "2_2") (pintype "passive"))
      (node (ref "U8") (pin "1") (pinfunction "VIN_1") (pintype "input"))
    )
    (net (code "84") (name "unconnected-(J1-DN2-PadB7)") (class "Default")
      (node (ref "J1") (pin "B7") (pinfunction "DN2_B7") (pintype "passive+no_connect"))
    )
    (net (code "85") (name "unconnected-(J1-DP2-PadB6)") (class "Default")
      (node (ref "J1") (pin "B6") (pinfunction "DP2_B6") (pintype "passive+no_connect"))
    )
    (net (code "86") (name "unconnected-(J1-SBU1-PadA8)") (class "Default")
      (node (ref "J1") (pin "A8") (pinfunction "SBU1_A8") (pintype "passive"))
    )
    (net (code "87") (name "unconnected-(J1-SBU2-PadB8)") (class "Default")
      (node (ref "J1") (pin "B8") (pinfunction "SBU2_B8") (pintype "passive"))
    )
    (net (code "88") (name "unconnected-(J3-Pad2)") (class "Default")
      (node (ref "J3") (pin "2") (pinfunction "2_2") (pintype "passive+no_connect"))
    )
    (net (code "89") (name "unconnected-(U3-ADKEY1-Pad12)") (class "Default")
      (node (ref "U3") (pin "12") (pinfunction "ADKEY1_12") (pintype "input+no_connect"))
    )
    (net (code "90") (name "unconnected-(U3-ADKEY2-Pad13)") (class "Default")
      (node (ref "U3") (pin "13") (pinfunction "ADKEY2_13") (pintype "input+no_connect"))
    )
    (net (code "91") (name "unconnected-(U3-IO1-Pad9)") (class "Default")
      (node (ref "U3") (pin "9") (pinfunction "IO1_9") (pintype "bidirectional+no_connect"))
    )
    (net (code "92") (name "unconnected-(U3-IO2-Pad11)") (class "Default")
      (node (ref "U3") (pin "11") (pinfunction "IO2_11") (pintype "bidirectional+no_connect"))
    )
    (net (code "93") (name "unconnected-(U3-SPK1-Pad6)") (class "Default")
      (node (ref "U3") (pin "6") (pinfunction "SPK1_6") (pintype "passive+no_connect"))
    )
    (net (code "94") (name "unconnected-(U3-SPK2-Pad8)") (class "Default")
      (node (ref "U3") (pin "8") (pinfunction "SPK2_8") (pintype "passive+no_connect"))
    )
    (net (code "95") (name "unconnected-(U3-USB+-Pad14)") (class "Default")
      (node (ref "U3") (pin "14") (pinfunction "USB+_14") (pintype "input+no_connect"))
    )
    (net (code "96") (name "unconnected-(U3-USB--Pad15)") (class "Default")
      (node (ref "U3") (pin "15") (pinfunction "USB-_15") (pintype "input+no_connect"))
    )
    (net (code "97") (name "unconnected-(U4-PadVBAT)") (class "Default")
      (node (ref "U4") (pin "VBAT") (pinfunction "VBAT_VBAT") (pintype "passive"))
    )
    (net (code "98") (name "unconnected-(U6-C-Pad9)") (class "Default")
      (node (ref "U6") (pin "9") (pinfunction "C_9") (pintype "input+no_connect"))
    )
    (net (code "99") (name "unconnected-(U6-IN{slash}OUT_CX-Pad5)") (class "Default")
      (node (ref "U6") (pin "5") (pinfunction "IN/OUT_CX_5") (pintype "input+no_connect"))
    )
    (net (code "100") (name "unconnected-(U6-IN{slash}OUT_CY-Pad3)") (class "Default")
      (node (ref "U6") (pin "3") (pinfunction "IN/OUT_CY_3") (pintype "input+no_connect"))
    )
    (net (code "101") (name "unconnected-(U6-OUT{slash}IN_CX_OR_CY-Pad4)") (class "Default")
      (node (ref "U6") (pin "4") (pinfunction "OUT/IN_CX_OR_CY_4") (pintype "output+no_connect"))
    )
  )
)
